# P01_Power.net
KiCad netlist of a schematic drawn in Altium Designer
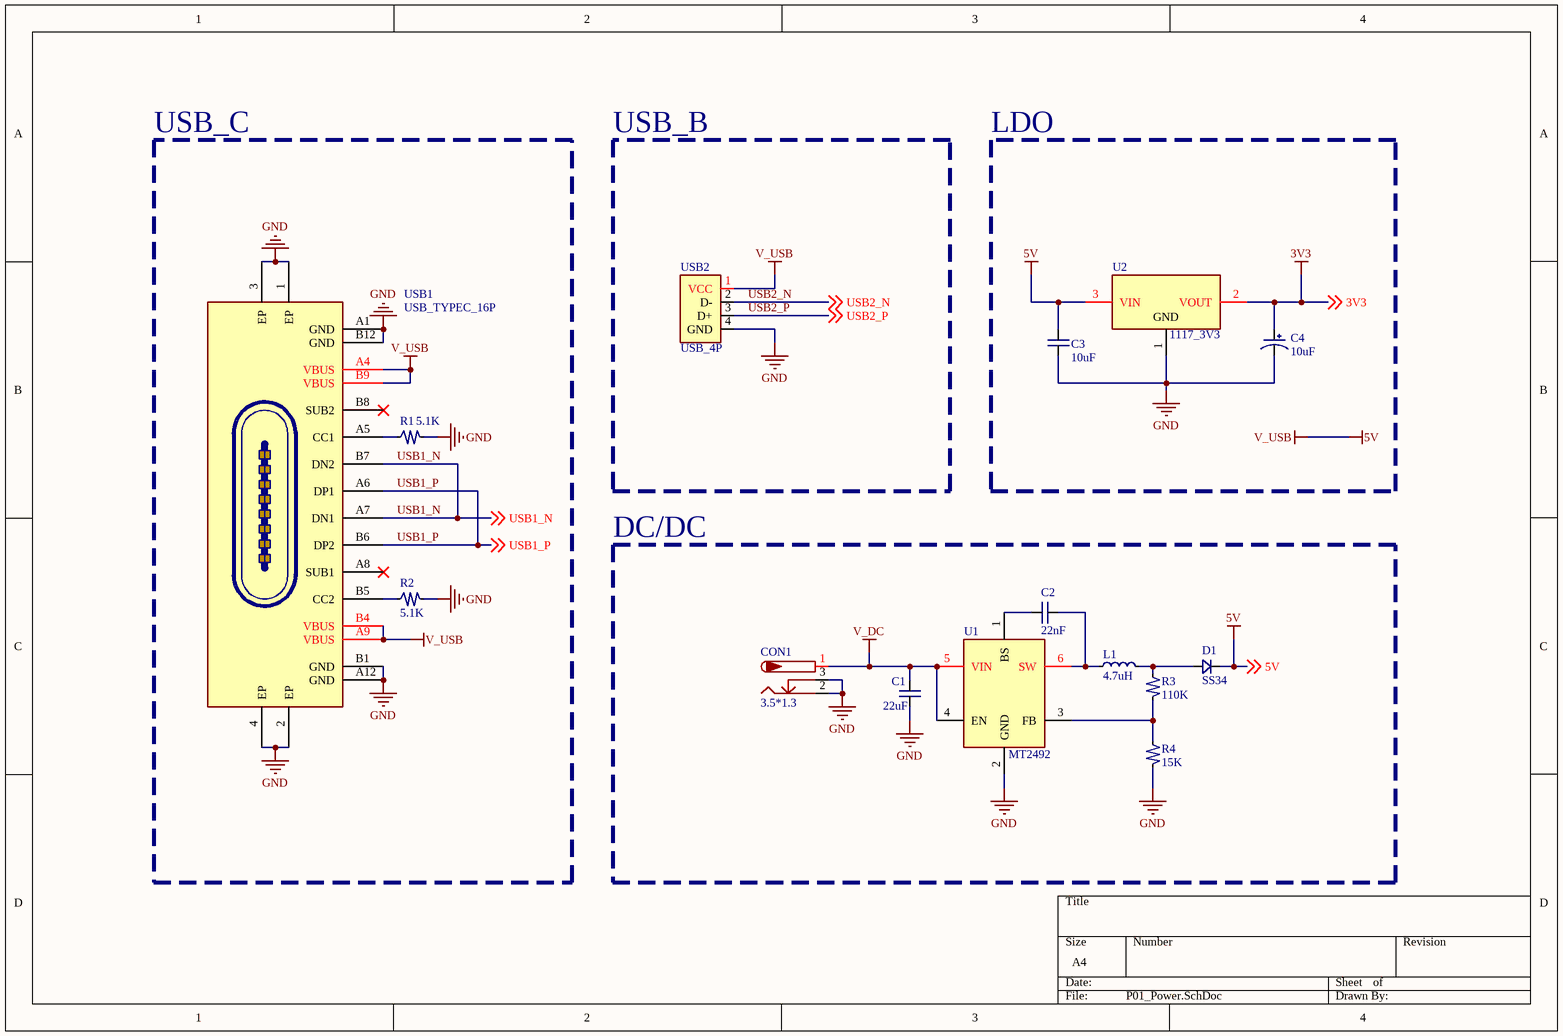
[diagram p0: P01_Power.SchDoc]

(export (version "E")
  (design (tool "Eeschema 10.0.6"))
  (components
    (comp (ref "C1")
      (value "22uF")
      (footprint "C_0603")
      (description "无极性电容")
      (libsource (lib "Schlib") (part "C"))
    )
    (comp (ref "C2")
      (value "22nF")
      (footprint "C_0603")
      (description "无极性电容")
      (libsource (lib "Schlib") (part "C"))
    )
    (comp (ref "C3")
      (value "10uF")
      (footprint "C_0805")
      (description "无极性电容")
      (libsource (lib "Schlib") (part "C"))
    )
    (comp (ref "C4")
      (value "10uF")
      (footprint "CASE-A-3216")
      (description "极性电容")
      (libsource (lib "Schlib") (part "C_P"))
    )
    (comp (ref "CON1")
      (value "3.5*1.3")
      (footprint "DC_Input")
      (description "低压电源接口")
      (libsource (lib "Schlib") (part "DC_Input"))
    )
    (comp (ref "D1")
      (value "SS34")
      (footprint "SMA")
      (description "二极管")
      (libsource (lib "Schlib") (part "D"))
    )
    (comp (ref "L1")
      (value "4.7uH")
      (footprint "L_SMD0420")
      (description "电感")
      (libsource (lib "Schlib") (part "L"))
    )
    (comp (ref "R1")
      (value "5.1K")
      (footprint "R_0402")
      (description "电阻")
      (libsource (lib "Schlib") (part "R"))
    )
    (comp (ref "R2")
      (value "5.1K")
      (footprint "R_0402")
      (description "电阻")
      (libsource (lib "Schlib") (part "R"))
    )
    (comp (ref "R3")
      (value "110K")
      (footprint "R_0603")
      (description "电阻")
      (libsource (lib "Schlib") (part "R"))
    )
    (comp (ref "R4")
      (value "15K")
      (footprint "R_0603")
      (description "电阻")
      (libsource (lib "Schlib") (part "R"))
    )
    (comp (ref "U1") (value "MT2492") (footprint "SOT-23-6") (libsource (lib "Schlib") (part "MT2492")))
    (comp (ref "U2")
      (value "1117_3V3")
      (footprint "SOT-223")
      (description "LDO to 3V3")
      (libsource (lib "Schlib") (part "1117_3V3"))
    )
    (comp (ref "USB1")
      (value "USB_TYPEC_16P")
      (footprint "USB_TYPEC_16P")
      (description "USB母座，TYPEC，16P")
      (libsource (lib "Schlib") (part "USB_TYPEC_16P"))
    )
    (comp (ref "USB2")
      (value "USB_4P")
      (footprint "USB_TYPEB_4P")
      (description "USB母座, 4P")
      (libsource (lib "Schlib") (part "USB_4Pin"))
    )
  )
  (nets
    (net (code "1") (name "3V3") (class "Default")
      (node (ref "C4") (pin "1") (pinfunction "1_1") (pintype "passive"))
      (node (ref "U2") (pin "2") (pinfunction "VOUT_2") (pintype "passive"))
    )
    (net (code "2") (name "5V") (class "Default")
      (node (ref "C3") (pin "1") (pinfunction "1_1") (pintype "passive"))
      (node (ref "D1") (pin "1") (pinfunction "1_1") (pintype "passive"))
      (node (ref "U2") (pin "3") (pinfunction "VIN_3") (pintype "passive"))
      (node (ref "USB1") (pin "A4") (pinfunction "VBUS_A4") (pintype "passive"))
      (node (ref "USB1") (pin "A9") (pinfunction "VBUS_A9") (pintype "passive"))
      (node (ref "USB1") (pin "B4") (pinfunction "VBUS_B4") (pintype "passive"))
      (node (ref "USB1") (pin "B9") (pinfunction "VBUS_B9") (pintype "passive"))
      (node (ref "USB2") (pin "1") (pinfunction "VCC_1") (pintype "passive"))
    )
    (net (code "3") (name "GND") (class "Default")
      (node (ref "C1") (pin "1") (pinfunction "1_1") (pintype "passive"))
      (node (ref "C3") (pin "2") (pinfunction "2_2") (pintype "passive"))
      (node (ref "C4") (pin "2") (pinfunction "2_2") (pintype "passive"))
      (node (ref "CON1") (pin "2") (pintype "power_in"))
      (node (ref "CON1") (pin "3") (pintype "power_in"))
      (node (ref "R1") (pin "1") (pinfunction "1_1") (pintype "passive"))
      (node (ref "R2") (pin "1") (pinfunction "1_1") (pintype "passive"))
      (node (ref "R4") (pin "1") (pinfunction "1_1") (pintype "passive"))
      (node (ref "U1") (pin "2") (pinfunction "GND_2") (pintype "passive"))
      (node (ref "U2") (pin "1") (pinfunction "GND_1") (pintype "passive"))
      (node (ref "USB1") (pin "1") (pinfunction "EP_1") (pintype "passive"))
      (node (ref "USB1") (pin "2") (pinfunction "EP_2") (pintype "passive"))
      (node (ref "USB1") (pin "3") (pinfunction "EP_3") (pintype "passive"))
      (node (ref "USB1") (pin "4") (pinfunction "EP_4") (pintype "passive"))
      (node (ref "USB1") (pin "A1") (pinfunction "GND_A1") (pintype "passive"))
      (node (ref "USB1") (pin "A12") (pinfunction "GND_A12") (pintype "passive"))
      (node (ref "USB1") (pin "B1") (pinfunction "GND_B1") (pintype "passive"))
      (node (ref "USB1") (pin "B12") (pinfunction "GND_B12") (pintype "passive"))
      (node (ref "USB2") (pin "4") (pinfunction "GND_4") (pintype "passive"))
    )
    (net (code "4") (name "Net-(D1-Pad2)") (class "Default")
      (node (ref "D1") (pin "2") (pinfunction "2_2") (pintype "passive"))
      (node (ref "L1") (pin "1") (pinfunction "1_1") (pintype "passive"))
      (node (ref "R3") (pin "2") (pinfunction "2_2") (pintype "passive"))
    )
    (net (code "5") (name "Net-(U1-BS)") (class "Default")
      (node (ref "C2") (pin "1") (pinfunction "1_1") (pintype "passive"))
      (node (ref "U1") (pin "1") (pinfunction "BS_1") (pintype "passive"))
    )
    (net (code "6") (name "Net-(U1-FB)") (class "Default")
      (node (ref "R3") (pin "1") (pinfunction "1_1") (pintype "passive"))
      (node (ref "R4") (pin "2") (pinfunction "2_2") (pintype "passive"))
      (node (ref "U1") (pin "3") (pinfunction "FB_3") (pintype "passive"))
    )
    (net (code "7") (name "Net-(U1-SW)") (class "Default")
      (node (ref "C2") (pin "2") (pinfunction "2_2") (pintype "passive"))
      (node (ref "L1") (pin "2") (pinfunction "2_2") (pintype "passive"))
      (node (ref "U1") (pin "6") (pinfunction "SW_6") (pintype "passive"))
    )
    (net (code "8") (name "Net-(USB1-CC1)") (class "Default")
      (node (ref "R1") (pin "2") (pinfunction "2_2") (pintype "passive"))
      (node (ref "USB1") (pin "A5") (pinfunction "CC1_A5") (pintype "passive"))
    )
    (net (code "9") (name "Net-(USB1-CC2)") (class "Default")
      (node (ref "R2") (pin "2") (pinfunction "2_2") (pintype "passive"))
      (node (ref "USB1") (pin "B5") (pinfunction "CC2_B5") (pintype "passive"))
    )
    (net (code "10") (name "USB1_N") (class "Default")
      (node (ref "USB1") (pin "A7") (pinfunction "DN1_A7") (pintype "passive"))
      (node (ref "USB1") (pin "B7") (pinfunction "DN2_B7") (pintype "passive"))
    )
    (net (code "11") (name "USB1_P") (class "Default")
      (node (ref "USB1") (pin "A6") (pinfunction "DP1_A6") (pintype "passive"))
      (node (ref "USB1") (pin "B6") (pinfunction "DP2_B6") (pintype "passive"))
    )
    (net (code "12") (name "USB2_N") (class "Default")
      (node (ref "USB2") (pin "2") (pinfunction "D-_2") (pintype "passive"))
    )
    (net (code "13") (name "USB2_P") (class "Default")
      (node (ref "USB2") (pin "3") (pinfunction "D+_3") (pintype "passive"))
    )
    (net (code "14") (name "V_DC") (class "Default")
      (node (ref "C1") (pin "2") (pinfunction "2_2") (pintype "passive"))
      (node (ref "CON1") (pin "1") (pintype "power_in"))
      (node (ref "U1") (pin "4") (pinfunction "EN_4") (pintype "passive"))
      (node (ref "U1") (pin "5") (pinfunction "VIN_5") (pintype "passive"))
    )
    (net (code "15") (name "unconnected-(USB1-SUB1-PadA8)") (class "Default")
      (node (ref "USB1") (pin "A8") (pinfunction "SUB1_A8") (pintype "passive+no_connect"))
    )
    (net (code "16") (name "unconnected-(USB1-SUB2-PadB8)") (class "Default")
      (node (ref "USB1") (pin "B8") (pinfunction "SUB2_B8") (pintype "passive+no_connect"))
    )
  )
)
